# mixer.net
KiCad netlist of a schematic drawn in Altium Designer
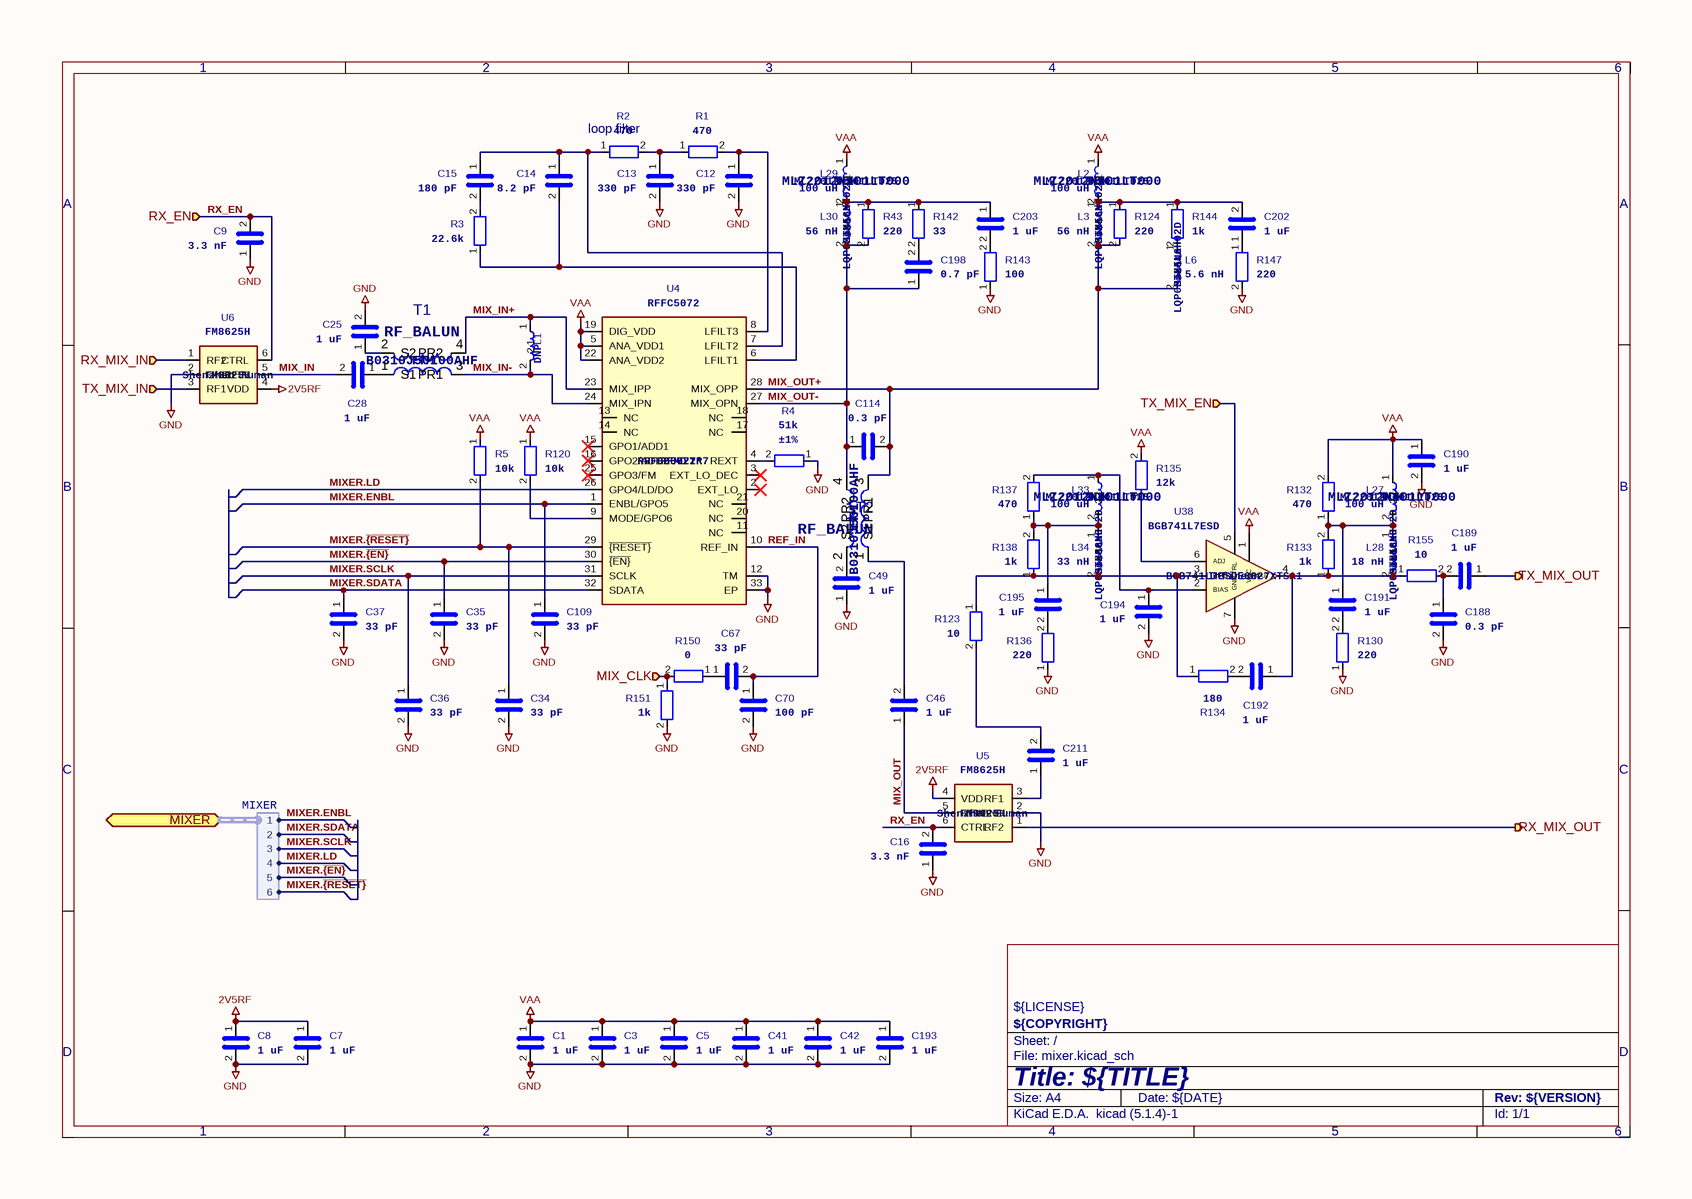
[diagram p0: mixer.SchDoc]

(export (version "E")
  (design (tool "Eeschema 10.0.6"))
  (components
    (comp (ref "C1")
      (value "1 uF")
      (footprint "C_0201_0603Metric")
      (fields (field (name "MANUFACTURER") "Murata") (field (name "PART NUMBER") "GRM033R61A105ME44D"))
      (libsource (lib "Device") (part "C"))
    )
    (comp (ref "C3")
      (value "1 uF")
      (footprint "C_0201_0603Metric")
      (fields (field (name "MANUFACTURER") "Murata") (field (name "PART NUMBER") "GRM033R61A105ME44D"))
      (libsource (lib "Device") (part "C"))
    )
    (comp (ref "C5")
      (value "1 uF")
      (footprint "C_0201_0603Metric")
      (fields (field (name "MANUFACTURER") "Murata") (field (name "PART NUMBER") "GRM033R61A105ME44D"))
      (libsource (lib "Device") (part "C"))
    )
    (comp (ref "C7")
      (value "1 uF")
      (footprint "C_0201_0603Metric")
      (fields (field (name "MANUFACTURER") "Murata") (field (name "PART NUMBER") "GRM033R61A105ME44D"))
      (libsource (lib "Device") (part "C"))
    )
    (comp (ref "C8")
      (value "1 uF")
      (footprint "C_0201_0603Metric")
      (fields (field (name "MANUFACTURER") "Murata") (field (name "PART NUMBER") "GRM033R61A105ME44D"))
      (libsource (lib "Device") (part "C"))
    )
    (comp (ref "C9")
      (value "3.3 nF")
      (footprint "C_0201_0603Metric")
      (fields (field (name "MANUFACTURER") "Murata") (field (name "PART NUMBER") "GRM033R71A332KA01D"))
      (libsource (lib "Device") (part "C"))
    )
    (comp (ref "C12")
      (value "330 pF")
      (footprint "C_0201_0603Metric")
      (fields (field (name "MANUFACTURER") "Murata") (field (name "PART NUMBER") "GRM0335C1E331JA01D"))
      (libsource (lib "Device") (part "C"))
    )
    (comp (ref "C13")
      (value "330 pF")
      (footprint "C_0201_0603Metric")
      (fields (field (name "MANUFACTURER") "Murata") (field (name "PART NUMBER") "GRM0335C1E331JA01D"))
      (libsource (lib "Device") (part "C"))
    )
    (comp (ref "C14")
      (value "8.2 pF")
      (footprint "C_0201_0603Metric")
      (fields (field (name "MANUFACTURER") "Murata") (field (name "PART NUMBER") "GRM0335C1H8R2CA01D"))
      (libsource (lib "Device") (part "C"))
    )
    (comp (ref "C15")
      (value "180 pF")
      (footprint "C_0201_0603Metric")
      (fields (field (name "MANUFACTURER") "Murata") (field (name "PART NUMBER") "GRM0335C1H181JA01D"))
      (libsource (lib "Device") (part "C"))
    )
    (comp (ref "C16")
      (value "3.3 nF")
      (footprint "C_0201_0603Metric")
      (fields (field (name "MANUFACTURER") "Murata") (field (name "PART NUMBER") "GRM033R71A332KA01D"))
      (libsource (lib "Device") (part "C"))
    )
    (comp (ref "C25")
      (value "1 uF")
      (footprint "C_0201_0603Metric")
      (fields (field (name "MANUFACTURER") "Murata") (field (name "PART NUMBER") "GRM033R61A105ME44D"))
      (libsource (lib "Device") (part "C"))
    )
    (comp (ref "C28")
      (value "1 uF")
      (footprint "C_0201_0603Metric")
      (fields (field (name "MANUFACTURER") "Murata") (field (name "PART NUMBER") "GRM033R61A105ME44D"))
      (libsource (lib "Device") (part "C"))
    )
    (comp (ref "C34")
      (value "33 pF")
      (footprint "C_0201_0603Metric")
      (fields (field (name "MANUFACTURER") "Murata") (field (name "PART NUMBER") "GRM0335C1H330JA01D"))
      (libsource (lib "Device") (part "C"))
    )
    (comp (ref "C35")
      (value "33 pF")
      (footprint "C_0201_0603Metric")
      (fields (field (name "MANUFACTURER") "Murata") (field (name "PART NUMBER") "GRM0335C1H330JA01D"))
      (libsource (lib "Device") (part "C"))
    )
    (comp (ref "C36")
      (value "33 pF")
      (footprint "C_0201_0603Metric")
      (fields (field (name "MANUFACTURER") "Murata") (field (name "PART NUMBER") "GRM0335C1H330JA01D"))
      (libsource (lib "Device") (part "C"))
    )
    (comp (ref "C37")
      (value "33 pF")
      (footprint "C_0201_0603Metric")
      (fields (field (name "MANUFACTURER") "Murata") (field (name "PART NUMBER") "GRM0335C1H330JA01D"))
      (libsource (lib "Device") (part "C"))
    )
    (comp (ref "C41")
      (value "1 uF")
      (footprint "C_0201_0603Metric")
      (fields (field (name "MANUFACTURER") "Murata") (field (name "PART NUMBER") "GRM033R61A105ME44D"))
      (libsource (lib "Device") (part "C"))
    )
    (comp (ref "C42")
      (value "1 uF")
      (footprint "C_0201_0603Metric")
      (fields (field (name "MANUFACTURER") "Murata") (field (name "PART NUMBER") "GRM033R61A105ME44D"))
      (libsource (lib "Device") (part "C"))
    )
    (comp (ref "C46")
      (value "1 uF")
      (footprint "C_0201_0603Metric")
      (fields (field (name "MANUFACTURER") "Murata") (field (name "PART NUMBER") "GRM033R61A105ME44D"))
      (libsource (lib "Device") (part "C"))
    )
    (comp (ref "C49")
      (value "1 uF")
      (footprint "C_0201_0603Metric")
      (fields (field (name "MANUFACTURER") "Murata") (field (name "PART NUMBER") "GRM033R61A105ME44D"))
      (libsource (lib "Device") (part "C"))
    )
    (comp (ref "C67")
      (value "33 pF")
      (footprint "C_0201_0603Metric")
      (fields (field (name "MANUFACTURER") "Murata") (field (name "PART NUMBER") "GRM0335C1H330JA01D"))
      (libsource (lib "Device") (part "C"))
    )
    (comp (ref "C70")
      (value "100 pF")
      (footprint "C_0201_0603Metric")
      (fields (field (name "MANUFACTURER") "Murata") (field (name "PART NUMBER") "GRM0335C1E101JA01D"))
      (libsource (lib "Device") (part "C"))
    )
    (comp (ref "C109")
      (value "33 pF")
      (footprint "C_0201_0603Metric")
      (fields (field (name "MANUFACTURER") "Murata") (field (name "PART NUMBER") "GRM0335C1H330JA01D"))
      (libsource (lib "Device") (part "C"))
    )
    (comp (ref "C114")
      (value "0.3 pF")
      (footprint "C_0201_0603Metric")
      (fields (field (name "MANUFACTURER") "Murata") (field (name "PART NUMBER") "GRM0335C1ER30BA01D"))
      (libsource (lib "Device") (part "C"))
    )
    (comp (ref "C188")
      (value "0.3 pF")
      (footprint "C_0201_0603Metric")
      (fields (field (name "MANUFACTURER") "Murata") (field (name "PART NUMBER") "GRM0335C1ER30BA01D"))
      (libsource (lib "Device") (part "C"))
    )
    (comp (ref "C189")
      (value "1 uF")
      (footprint "C_0201_0603Metric")
      (fields (field (name "MANUFACTURER") "Murata") (field (name "PART NUMBER") "GRM033R61A105ME44D"))
      (libsource (lib "Device") (part "C"))
    )
    (comp (ref "C190")
      (value "1 uF")
      (footprint "C_0201_0603Metric")
      (fields (field (name "MANUFACTURER") "Murata") (field (name "PART NUMBER") "GRM033R61A105ME44D"))
      (libsource (lib "Device") (part "C"))
    )
    (comp (ref "C191")
      (value "1 uF")
      (footprint "C_0201_0603Metric")
      (fields (field (name "MANUFACTURER") "Murata") (field (name "PART NUMBER") "GRM033R61A105ME44D"))
      (libsource (lib "Device") (part "C"))
    )
    (comp (ref "C192")
      (value "1 uF")
      (footprint "C_0201_0603Metric")
      (fields (field (name "MANUFACTURER") "Murata") (field (name "PART NUMBER") "GRM033R61A105ME44D"))
      (libsource (lib "Device") (part "C"))
    )
    (comp (ref "C193")
      (value "1 uF")
      (footprint "C_0201_0603Metric")
      (fields (field (name "MANUFACTURER") "Murata") (field (name "PART NUMBER") "GRM033R61A105ME44D"))
      (libsource (lib "Device") (part "C"))
    )
    (comp (ref "C194")
      (value "1 uF")
      (footprint "C_0201_0603Metric")
      (fields (field (name "MANUFACTURER") "Murata") (field (name "PART NUMBER") "GRM033R61A105ME44D"))
      (libsource (lib "Device") (part "C"))
    )
    (comp (ref "C195")
      (value "1 uF")
      (footprint "C_0201_0603Metric")
      (fields (field (name "MANUFACTURER") "Murata") (field (name "PART NUMBER") "GRM033R61A105ME44D"))
      (libsource (lib "Device") (part "C"))
    )
    (comp (ref "C198")
      (value "0.7 pF")
      (footprint "C_0201_0603Metric")
      (fields (field (name "MANUFACTURER") "Murata") (field (name "PART NUMBER") "GRM0335C1ER70WA01D"))
      (libsource (lib "Device") (part "C"))
    )
    (comp (ref "C202")
      (value "1 uF")
      (footprint "C_0201_0603Metric")
      (fields (field (name "MANUFACTURER") "Murata") (field (name "PART NUMBER") "GRM033R61A105ME44D"))
      (libsource (lib "Device") (part "C"))
    )
    (comp (ref "C203")
      (value "1 uF")
      (footprint "C_0201_0603Metric")
      (fields (field (name "MANUFACTURER") "Murata") (field (name "PART NUMBER") "GRM033R61A105ME44D"))
      (libsource (lib "Device") (part "C"))
    )
    (comp (ref "C211")
      (value "1 uF")
      (footprint "C_0201_0603Metric")
      (fields (field (name "MANUFACTURER") "Murata") (field (name "PART NUMBER") "GRM033R61A105ME44D"))
      (libsource (lib "Device") (part "C"))
    )
    (comp (ref "L1") (value "DNP") (footprint "L_0201_0603Metric") (libsource (lib "Device") (part "L")))
    (comp (ref "L2")
      (value "100 uH")
      (footprint "L_TDK_MLZ2012_h1.25mm")
      (fields
        (field (name "MANUFACTURER") "TDK")
        (field (name "PART NUMBER") "MLZ2012N101LT000")
        (field (name "SUBSTITUTION") "MLZ2012N101LTD25")
      )
      (libsource (lib "") (part "L_1"))
    )
    (comp (ref "L3")
      (value "56 nH")
      (footprint "L_0201_0603Metric")
      (fields
        (field (name "MANUFACTURER") "Murata")
        (field (name "PART NUMBER") "LQP03TN56NJ02D")
        (field (name "SUBSTITUTION") "LQP03TN56NH02D")
      )
      (libsource (lib "Device") (part "L"))
    )
    (comp (ref "L6")
      (value "5.6 nH")
      (footprint "L_0201_0603Metric")
      (fields (field (name "MANUFACTURER") "Murata") (field (name "PART NUMBER") "LQP03TN5N6H02D"))
      (libsource (lib "Device") (part "L"))
    )
    (comp (ref "L27")
      (value "100 uH")
      (footprint "L_TDK_MLZ2012_h1.25mm")
      (fields
        (field (name "MANUFACTURER") "TDK")
        (field (name "PART NUMBER") "MLZ2012N101LT000")
        (field (name "SUBSTITUTION") "MLZ2012N101LTD25")
      )
      (libsource (lib "Device") (part "L"))
    )
    (comp (ref "L28")
      (value "18 nH")
      (footprint "L_0201_0603Metric")
      (fields
        (field (name "MANUFACTURER") "Murata")
        (field (name "PART NUMBER") "LQP03TN18NJ02D")
        (field (name "SUBSTITUTION") "LQP03TN56NH02D")
      )
      (libsource (lib "Device") (part "L"))
    )
    (comp (ref "L29")
      (value "100 uH")
      (footprint "L_TDK_MLZ2012_h1.25mm")
      (fields
        (field (name "MANUFACTURER") "TDK")
        (field (name "PART NUMBER") "MLZ2012N101LT000")
        (field (name "SUBSTITUTION") "MLZ2012N101LTD25")
      )
      (libsource (lib "") (part "L_1"))
    )
    (comp (ref "L30")
      (value "56 nH")
      (footprint "L_0201_0603Metric")
      (fields
        (field (name "MANUFACTURER") "Murata")
        (field (name "PART NUMBER") "LQP03TN56NJ02D")
        (field (name "SUBSTITUTION") "LQP03TN56NH02D")
      )
      (libsource (lib "Device") (part "L"))
    )
    (comp (ref "L33")
      (value "100 uH")
      (footprint "L_TDK_MLZ2012_h1.25mm")
      (fields
        (field (name "MANUFACTURER") "TDK")
        (field (name "PART NUMBER") "MLZ2012N101LT000")
        (field (name "SUBSTITUTION") "MLZ2012N101LTD25")
      )
      (libsource (lib "Device") (part "L"))
    )
    (comp (ref "L34")
      (value "33 nH")
      (footprint "L_0201_0603Metric")
      (fields
        (field (name "MANUFACTURER") "Murata")
        (field (name "PART NUMBER") "LQP03TN33NJ02D")
        (field (name "SUBSTITUTION") "LQP03TN56NH02D")
      )
      (libsource (lib "Device") (part "L"))
    )
    (comp (ref "R1")
      (value "470")
      (footprint "R_0201_0603Metric")
      (fields (field (name "MANUFACTURER") "Yageo") (field (name "PART NUMBER") "RC0201JR-07470RL"))
      (libsource (lib "Device") (part "R"))
    )
    (comp (ref "R2")
      (value "470")
      (footprint "R_0201_0603Metric")
      (fields (field (name "MANUFACTURER") "Yageo") (field (name "PART NUMBER") "RC0201JR-07470RL"))
      (libsource (lib "Device") (part "R"))
    )
    (comp (ref "R3")
      (value "22.6k")
      (footprint "R_0201_0603Metric")
      (fields (field (name "MANUFACTURER") "Yageo") (field (name "PART NUMBER") "RC0201FR-0722K6L"))
      (libsource (lib "") (part "R_1"))
    )
    (comp (ref "R4")
      (value "51k")
      (footprint "R_0201_0603Metric")
      (fields
        (field (name "MANUFACTURER") "Yageo")
        (field (name "PART NUMBER") "RC0201FR-0751KL")
        (field (name "TOLERANCE") "±1%")
      )
      (libsource (lib "") (part "R_3"))
    )
    (comp (ref "R5")
      (value "10k")
      (footprint "R_0402_1005Metric")
      (fields (field (name "MANUFACTURER") "Yageo") (field (name "PART NUMBER") "RC0402JR-0710KL"))
      (libsource (lib "") (part "R_2"))
    )
    (comp (ref "R43")
      (value "220")
      (footprint "R_0201_0603Metric")
      (fields (field (name "MANUFACTURER") "Yageo") (field (name "PART NUMBER") "RC0201JR-07220RL"))
      (libsource (lib "") (part "R_2"))
    )
    (comp (ref "R120")
      (value "10k")
      (footprint "R_0402_1005Metric")
      (fields (field (name "MANUFACTURER") "Yageo") (field (name "PART NUMBER") "RC0402JR-0710KL"))
      (libsource (lib "") (part "R_2"))
    )
    (comp (ref "R123")
      (value "10")
      (footprint "R_0201_0603Metric")
      (fields (field (name "MANUFACTURER") "Yageo") (field (name "PART NUMBER") "RC0201JR-0710RL"))
      (libsource (lib "") (part "R_2"))
    )
    (comp (ref "R124")
      (value "220")
      (footprint "R_0201_0603Metric")
      (fields (field (name "MANUFACTURER") "Yageo") (field (name "PART NUMBER") "RC0201JR-07220RL"))
      (libsource (lib "") (part "R_2"))
    )
    (comp (ref "R130")
      (value "220")
      (footprint "R_0201_0603Metric")
      (fields (field (name "MANUFACTURER") "Yageo") (field (name "PART NUMBER") "RC0201JR-07220RL"))
      (libsource (lib "Device") (part "R"))
    )
    (comp (ref "R132")
      (value "470")
      (footprint "R_0201_0603Metric")
      (fields (field (name "MANUFACTURER") "Yageo") (field (name "PART NUMBER") "RC0201JR-07470RL"))
      (libsource (lib "") (part "R_1"))
    )
    (comp (ref "R133")
      (value "1k")
      (footprint "R_0201_0603Metric")
      (fields (field (name "MANUFACTURER") "Yageo") (field (name "PART NUMBER") "RC0201FR-071KL"))
      (libsource (lib "") (part "R_1"))
    )
    (comp (ref "R134")
      (value "180")
      (footprint "R_0201_0603Metric")
      (fields (field (name "MANUFACTURER") "Yageo") (field (name "PART NUMBER") "RC0201JR-07180RL"))
      (libsource (lib "Device") (part "R"))
    )
    (comp (ref "R135")
      (value "12k")
      (footprint "R_0201_0603Metric")
      (fields (field (name "PART NUMBER") "RC0201FR-0712KL") (field (name "MANUFACTURER") "Yageo"))
      (libsource (lib "Device") (part "R"))
    )
    (comp (ref "R136")
      (value "220")
      (footprint "R_0201_0603Metric")
      (fields (field (name "MANUFACTURER") "Yageo") (field (name "PART NUMBER") "RC0201JR-07220RL"))
      (libsource (lib "") (part "R_1"))
    )
    (comp (ref "R137")
      (value "470")
      (footprint "R_0201_0603Metric")
      (fields (field (name "MANUFACTURER") "Yageo") (field (name "PART NUMBER") "RC0201JR-07470RL"))
      (libsource (lib "") (part "R_1"))
    )
    (comp (ref "R138")
      (value "1k")
      (footprint "R_0201_0603Metric")
      (fields (field (name "MANUFACTURER") "Yageo") (field (name "PART NUMBER") "RC0201FR-071KL"))
      (libsource (lib "") (part "R_1"))
    )
    (comp (ref "R142")
      (value "33")
      (footprint "R_0201_0603Metric")
      (fields (field (name "MANUFACTURER") "Yageo") (field (name "PART NUMBER") "RC0201JR-0733RL"))
      (libsource (lib "") (part "R_3"))
    )
    (comp (ref "R143")
      (value "100")
      (footprint "R_0201_0603Metric")
      (fields (field (name "MANUFACTURER") "Yageo") (field (name "PART NUMBER") "RC0201JR-07100RL"))
      (libsource (lib "Device") (part "R"))
    )
    (comp (ref "R144")
      (value "1k")
      (footprint "R_0201_0603Metric")
      (fields (field (name "MANUFACTURER") "Yageo") (field (name "PART NUMBER") "RC0201FR-071KL"))
      (libsource (lib "") (part "R_3"))
    )
    (comp (ref "R147")
      (value "220")
      (footprint "R_0201_0603Metric")
      (fields (field (name "MANUFACTURER") "Yageo") (field (name "PART NUMBER") "RC0201JR-07220RL"))
      (libsource (lib "") (part "R_2"))
    )
    (comp (ref "R150")
      (value "0")
      (footprint "R_0201_0603Metric")
      (fields (field (name "MANUFACTURER") "Yageo") (field (name "PART NUMBER") "RC0201JR-070RL"))
      (libsource (lib "") (part "R_2"))
    )
    (comp (ref "R151")
      (value "1k")
      (footprint "R_0201_0603Metric")
      (fields (field (name "MANUFACTURER") "Yageo") (field (name "PART NUMBER") "RC0201FR-071KL"))
      (libsource (lib "") (part "R_3"))
    )
    (comp (ref "R155")
      (value "10")
      (footprint "R_0201_0603Metric")
      (fields (field (name "MANUFACTURER") "Yageo") (field (name "PART NUMBER") "RC0201JR-0710RL"))
      (libsource (lib "") (part "R_1"))
    )
    (comp (ref "T1")
      (value "RF_BALUN")
      (footprint "Anaren_0805_2012Metric-6")
      (fields (field (name "MANUFACTURER") "TTM") (field (name "PART NUMBER") "B0310J50100AHF"))
      (libsource (lib "hackrf") (part "BALUN-B0310J50100AHF"))
    )
    (comp (ref "T2")
      (value "RF_BALUN")
      (footprint "Anaren_0805_2012Metric-6")
      (fields (field (name "MANUFACTURER") "TTM") (field (name "PART NUMBER") "B0310J50100AHF"))
      (libsource (lib "hackrf") (part "BALUN-B0310J50100AHF"))
    )
    (comp (ref "U4")
      (value "RFFC5072")
      (footprint "QFN-32-1EP_5x5mm_P0.5mm_EP3.7x3.7mm_ThermalVias")
      (fields
        (field (name "MANUFACTURER") "RFMD")
        (field (name "PART NUMBER") "RFFC5072TR7")
        (field (name "SUBSTITUTION") "RFFC5072*")
      )
      (libsource (lib "praline") (part "RFFC5072"))
    )
    (comp (ref "U5")
      (value "FM8625H")
      (footprint "TSLP-6-4_1.1x0.7mm_P0.4mm")
      (fields (field (name "MANUFACTURER") "Shenzhen Fuman") (field (name "PART NUMBER") "FM8625H"))
      (libsource (lib "") (part "BGS12P2L6_1"))
    )
    (comp (ref "U6")
      (value "FM8625H")
      (footprint "TSLP-6-4_1.1x0.7mm_P0.4mm")
      (fields (field (name "MANUFACTURER") "Shenzhen Fuman") (field (name "PART NUMBER") "FM8625H"))
      (libsource (lib "praline") (part "BGS12P2L6"))
    )
    (comp (ref "U38")
      (value "BGB741L7ESD")
      (footprint "TSLP-7-1")
      (fields (field (name "MANUFACTURER") "Infineon") (field (name "PART NUMBER") "BGB741L7ESDE6327XTSA1"))
      (libsource (lib "praline") (part "BGB741L7ESD"))
    )
  )
  (nets
    (net (code "2") (name "/MIXER.ENBL") (class "Default")
      (node (ref "C109") (pin "1") (pinfunction "1_1") (pintype "passive"))
      (node (ref "U4") (pin "1") (pinfunction "ENBL/GPO5_1") (pintype "passive"))
    )
    (net (code "3") (name "/MIXER.LD") (class "Default")
      (node (ref "U4") (pin "26") (pinfunction "GPO4/LD/DO_26") (pintype "passive"))
    )
    (net (code "4") (name "/MIXER.SCLK") (class "Default")
      (node (ref "C36") (pin "1") (pinfunction "1_1") (pintype "passive"))
      (node (ref "U4") (pin "31") (pinfunction "SCLK_31") (pintype "passive"))
    )
    (net (code "5") (name "/MIXER.SDATA") (class "Default")
      (node (ref "C37") (pin "1") (pinfunction "1_1") (pintype "passive"))
      (node (ref "U4") (pin "32") (pinfunction "SDATA_32") (pintype "passive"))
    )
    (net (code "6") (name "/MIXER.~{{EN}}") (class "Default")
      (node (ref "C35") (pin "1") (pinfunction "1_1") (pintype "passive"))
      (node (ref "U4") (pin "30") (pinfunction "~{{EN}}_30") (pintype "passive"))
    )
    (net (code "7") (name "/MIXER.~{{RESET}}") (class "Default")
      (node (ref "C34") (pin "1") (pinfunction "1_1") (pintype "passive"))
      (node (ref "R5") (pin "2") (pinfunction "2_2") (pintype "passive"))
      (node (ref "U4") (pin "29") (pinfunction "~{{RESET}}_29") (pintype "passive"))
    )
    (net (code "8") (name "/MIX_CLK") (class "Default")
      (node (ref "R150") (pin "2") (pinfunction "2_2") (pintype "passive"))
      (node (ref "R151") (pin "1") (pinfunction "1_1") (pintype "passive"))
    )
    (net (code "9") (name "/MIX_IN") (class "Default")
      (node (ref "C28") (pin "2") (pinfunction "2_2") (pintype "passive"))
      (node (ref "U6") (pin "5") (pinfunction "RFIN_5") (pintype "passive"))
    )
    (net (code "10") (name "/MIX_IN+") (class "Default")
      (node (ref "L1") (pin "1") (pinfunction "1_1") (pintype "passive"))
      (node (ref "T1") (pin "4") (pinfunction "PR2_4") (pintype "passive"))
      (node (ref "U4") (pin "23") (pinfunction "MIX_IPP_23") (pintype "passive"))
    )
    (net (code "11") (name "/MIX_IN-") (class "Default")
      (node (ref "L1") (pin "2") (pinfunction "2_2") (pintype "passive"))
      (node (ref "T1") (pin "3") (pinfunction "PR1_3") (pintype "passive"))
      (node (ref "U4") (pin "24") (pinfunction "MIX_IPN_24") (pintype "passive"))
    )
    (net (code "12") (name "/MIX_OUT") (class "Default")
      (node (ref "C46") (pin "1") (pinfunction "1_1") (pintype "passive"))
      (node (ref "U5") (pin "5") (pinfunction "RFIN_5") (pintype "passive"))
    )
    (net (code "13") (name "/MIX_OUT+") (class "Default")
      (node (ref "C114") (pin "2") (pinfunction "2_2") (pintype "passive"))
      (node (ref "L3") (pin "2") (pinfunction "2_2") (pintype "passive"))
      (node (ref "L6") (pin "2") (pinfunction "2_2") (pintype "passive"))
      (node (ref "R124") (pin "2") (pinfunction "2_2") (pintype "passive"))
      (node (ref "T2") (pin "3") (pinfunction "PR1_3") (pintype "passive"))
      (node (ref "U4") (pin "28") (pinfunction "MIX_OPP_28") (pintype "passive"))
    )
    (net (code "14") (name "/MIX_OUT-") (class "Default")
      (node (ref "C114") (pin "1") (pinfunction "1_1") (pintype "passive"))
      (node (ref "C198") (pin "1") (pinfunction "1_1") (pintype "passive"))
      (node (ref "L30") (pin "2") (pinfunction "2_2") (pintype "passive"))
      (node (ref "R43") (pin "2") (pinfunction "2_2") (pintype "passive"))
      (node (ref "T2") (pin "4") (pinfunction "PR2_4") (pintype "passive"))
      (node (ref "U4") (pin "27") (pinfunction "MIX_OPN_27") (pintype "passive"))
    )
    (net (code "15") (name "/REF_IN") (class "Default")
      (node (ref "C67") (pin "2") (pinfunction "2_2") (pintype "passive"))
      (node (ref "C70") (pin "1") (pinfunction "1_1") (pintype "passive"))
      (node (ref "U4") (pin "10") (pinfunction "REF_IN_10") (pintype "passive"))
    )
    (net (code "16") (name "/RX_EN") (class "Default")
      (node (ref "C16") (pin "2") (pinfunction "2_2") (pintype "passive"))
      (node (ref "C9") (pin "2") (pinfunction "2_2") (pintype "passive"))
      (node (ref "U5") (pin "6") (pinfunction "CTRL_6") (pintype "passive"))
      (node (ref "U6") (pin "6") (pinfunction "CTRL_6") (pintype "passive"))
    )
    (net (code "17") (name "/RX_MIX_IN") (class "Default")
      (node (ref "U6") (pin "1") (pinfunction "RF2_1") (pintype "passive"))
    )
    (net (code "18") (name "/RX_MIX_OUT") (class "Default")
      (node (ref "U5") (pin "1") (pinfunction "RF2_1") (pintype "passive"))
    )
    (net (code "19") (name "/TX_MIX_EN") (class "Default")
      (node (ref "U38") (pin "5") (pinfunction "CTRL_5") (pintype "passive"))
    )
    (net (code "20") (name "/TX_MIX_IN") (class "Default")
      (node (ref "U6") (pin "3") (pinfunction "RF1_3") (pintype "passive"))
    )
    (net (code "21") (name "/TX_MIX_OUT") (class "Default")
      (node (ref "C189") (pin "1") (pinfunction "1_1") (pintype "passive"))
    )
    (net (code "23") (name "2V5RF") (class "Default")
      (node (ref "C7") (pin "1") (pinfunction "1_1") (pintype "passive"))
      (node (ref "C8") (pin "1") (pinfunction "1_1") (pintype "passive"))
      (node (ref "U5") (pin "4") (pinfunction "VDD_4") (pintype "passive"))
      (node (ref "U6") (pin "4") (pinfunction "VDD_4") (pintype "passive"))
    )
    (net (code "24") (name "GND") (class "Default")
      (node (ref "C1") (pin "2") (pinfunction "2_2") (pintype "passive"))
      (node (ref "C109") (pin "2") (pinfunction "2_2") (pintype "passive"))
      (node (ref "C12") (pin "2") (pinfunction "2_2") (pintype "passive"))
      (node (ref "C13") (pin "2") (pinfunction "2_2") (pintype "passive"))
      (node (ref "C16") (pin "1") (pinfunction "1_1") (pintype "passive"))
      (node (ref "C188") (pin "2") (pinfunction "2_2") (pintype "passive"))
      (node (ref "C190") (pin "2") (pinfunction "2_2") (pintype "passive"))
      (node (ref "C193") (pin "2") (pinfunction "2_2") (pintype "passive"))
      (node (ref "C194") (pin "2") (pinfunction "2_2") (pintype "passive"))
      (node (ref "C25") (pin "2") (pinfunction "2_2") (pintype "passive"))
      (node (ref "C3") (pin "2") (pinfunction "2_2") (pintype "passive"))
      (node (ref "C34") (pin "2") (pinfunction "2_2") (pintype "passive"))
      (node (ref "C35") (pin "2") (pinfunction "2_2") (pintype "passive"))
      (node (ref "C36") (pin "2") (pinfunction "2_2") (pintype "passive"))
      (node (ref "C37") (pin "2") (pinfunction "2_2") (pintype "passive"))
      (node (ref "C41") (pin "2") (pinfunction "2_2") (pintype "passive"))
      (node (ref "C42") (pin "2") (pinfunction "2_2") (pintype "passive"))
      (node (ref "C49") (pin "1") (pinfunction "1_1") (pintype "passive"))
      (node (ref "C5") (pin "2") (pinfunction "2_2") (pintype "passive"))
      (node (ref "C7") (pin "2") (pinfunction "2_2") (pintype "passive"))
      (node (ref "C70") (pin "2") (pinfunction "2_2") (pintype "passive"))
      (node (ref "C8") (pin "2") (pinfunction "2_2") (pintype "passive"))
      (node (ref "C9") (pin "1") (pinfunction "1_1") (pintype "passive"))
      (node (ref "R130") (pin "1") (pinfunction "1_1") (pintype "passive"))
      (node (ref "R136") (pin "1") (pinfunction "1_1") (pintype "passive"))
      (node (ref "R143") (pin "1") (pinfunction "1_1") (pintype "passive"))
      (node (ref "R147") (pin "2") (pinfunction "2_2") (pintype "passive"))
      (node (ref "R151") (pin "2") (pinfunction "2_2") (pintype "passive"))
      (node (ref "R4") (pin "1") (pinfunction "1_1") (pintype "passive"))
      (node (ref "U38") (pin "7") (pinfunction "GND_7") (pintype "passive"))
      (node (ref "U4") (pin "12") (pinfunction "TM_12") (pintype "passive"))
      (node (ref "U4") (pin "33") (pinfunction "EP_33") (pintype "passive"))
      (node (ref "U5") (pin "2") (pinfunction "GND_2") (pintype "passive"))
      (node (ref "U6") (pin "2") (pinfunction "GND_2") (pintype "passive"))
    )
    (net (code "25") (name "Net-(C13-Pad1)") (class "Default")
      (node (ref "C13") (pin "1") (pinfunction "1_1") (pintype "passive"))
      (node (ref "R1") (pin "1") (pinfunction "1_1") (pintype "passive"))
      (node (ref "R2") (pin "2") (pinfunction "2_2") (pintype "passive"))
    )
    (net (code "26") (name "Net-(C15-Pad2)") (class "Default")
      (node (ref "C15") (pin "2") (pinfunction "2_2") (pintype "passive"))
      (node (ref "R3") (pin "2") (pinfunction "2_2") (pintype "passive"))
    )
    (net (code "27") (name "Net-(C67-Pad1)") (class "Default")
      (node (ref "C67") (pin "1") (pinfunction "1_1") (pintype "passive"))
      (node (ref "R150") (pin "1") (pinfunction "1_1") (pintype "passive"))
    )
    (net (code "28") (name "Net-(C188-Pad1)") (class "Default")
      (node (ref "C188") (pin "1") (pinfunction "1_1") (pintype "passive"))
      (node (ref "C189") (pin "2") (pinfunction "2_2") (pintype "passive"))
      (node (ref "R155") (pin "2") (pinfunction "2_2") (pintype "passive"))
    )
    (net (code "29") (name "Net-(C191-Pad1)") (class "Default")
      (node (ref "C191") (pin "1") (pinfunction "1_1") (pintype "passive"))
      (node (ref "L27") (pin "2") (pinfunction "2_2") (pintype "passive"))
      (node (ref "L28") (pin "1") (pinfunction "1_1") (pintype "passive"))
      (node (ref "R132") (pin "1") (pinfunction "1_1") (pintype "passive"))
      (node (ref "R133") (pin "2") (pinfunction "2_2") (pintype "passive"))
    )
    (net (code "30") (name "Net-(C191-Pad2)") (class "Default")
      (node (ref "C191") (pin "2") (pinfunction "2_2") (pintype "passive"))
      (node (ref "R130") (pin "2") (pinfunction "2_2") (pintype "passive"))
    )
    (net (code "31") (name "Net-(C192-Pad2)") (class "Default")
      (node (ref "C192") (pin "2") (pinfunction "2_2") (pintype "passive"))
      (node (ref "R134") (pin "2") (pinfunction "2_2") (pintype "passive"))
    )
    (net (code "32") (name "Net-(C195-Pad1)") (class "Default")
      (node (ref "C195") (pin "1") (pinfunction "1_1") (pintype "passive"))
      (node (ref "L33") (pin "2") (pinfunction "2_2") (pintype "passive"))
      (node (ref "L34") (pin "1") (pinfunction "1_1") (pintype "passive"))
      (node (ref "R137") (pin "1") (pinfunction "1_1") (pintype "passive"))
      (node (ref "R138") (pin "2") (pinfunction "2_2") (pintype "passive"))
    )
    (net (code "33") (name "Net-(C195-Pad2)") (class "Default")
      (node (ref "C195") (pin "2") (pinfunction "2_2") (pintype "passive"))
      (node (ref "R136") (pin "2") (pinfunction "2_2") (pintype "passive"))
    )
    (net (code "34") (name "Net-(C198-Pad2)") (class "Default")
      (node (ref "C198") (pin "2") (pinfunction "2_2") (pintype "passive"))
      (node (ref "R142") (pin "2") (pinfunction "2_2") (pintype "passive"))
    )
    (net (code "35") (name "Net-(C202-Pad1)") (class "Default")
      (node (ref "C202") (pin "1") (pinfunction "1_1") (pintype "passive"))
      (node (ref "R147") (pin "1") (pinfunction "1_1") (pintype "passive"))
    )
    (net (code "36") (name "Net-(C202-Pad2)") (class "Default")
      (node (ref "C202") (pin "2") (pinfunction "2_2") (pintype "passive"))
      (node (ref "L2") (pin "2") (pinfunction "2_2") (pintype "passive"))
      (node (ref "L3") (pin "1") (pinfunction "1_1") (pintype "passive"))
      (node (ref "R124") (pin "1") (pinfunction "1_1") (pintype "passive"))
      (node (ref "R144") (pin "1") (pinfunction "1_1") (pintype "passive"))
    )
    (net (code "37") (name "Net-(C203-Pad1)") (class "Default")
      (node (ref "C203") (pin "1") (pinfunction "1_1") (pintype "passive"))
      (node (ref "L29") (pin "2") (pinfunction "2_2") (pintype "passive"))
      (node (ref "L30") (pin "1") (pinfunction "1_1") (pintype "passive"))
      (node (ref "R142") (pin "1") (pinfunction "1_1") (pintype "passive"))
      (node (ref "R43") (pin "1") (pinfunction "1_1") (pintype "passive"))
    )
    (net (code "38") (name "Net-(C203-Pad2)") (class "Default")
      (node (ref "C203") (pin "2") (pinfunction "2_2") (pintype "passive"))
      (node (ref "R143") (pin "2") (pinfunction "2_2") (pintype "passive"))
    )
    (net (code "39") (name "Net-(C211-Pad2)") (class "Default")
      (node (ref "C211") (pin "2") (pinfunction "2_2") (pintype "passive"))
      (node (ref "R123") (pin "2") (pinfunction "2_2") (pintype "passive"))
    )
    (net (code "40") (name "Net-(L6-Pad1)") (class "Default")
      (node (ref "L6") (pin "1") (pinfunction "1_1") (pintype "passive"))
      (node (ref "R144") (pin "2") (pinfunction "2_2") (pintype "passive"))
    )
    (net (code "41") (name "Net-(T1-S1)") (class "Default")
      (node (ref "C28") (pin "1") (pinfunction "1_1") (pintype "passive"))
      (node (ref "T1") (pin "1") (pinfunction "S1_1") (pintype "passive"))
    )
    (net (code "42") (name "Net-(T1-S2)") (class "Default")
      (node (ref "C25") (pin "1") (pinfunction "1_1") (pintype "passive"))
      (node (ref "T1") (pin "2") (pinfunction "S2_2") (pintype "passive"))
    )
    (net (code "43") (name "Net-(T2-S1)") (class "Default")
      (node (ref "C46") (pin "2") (pinfunction "2_2") (pintype "passive"))
      (node (ref "T2") (pin "1") (pinfunction "S1_1") (pintype "passive"))
    )
    (net (code "44") (name "Net-(T2-S2)") (class "Default")
      (node (ref "C49") (pin "2") (pinfunction "2_2") (pintype "passive"))
      (node (ref "T2") (pin "2") (pinfunction "S2_2") (pintype "passive"))
    )
    (net (code "45") (name "Net-(U4-LFILT1)") (class "Default")
      (node (ref "C14") (pin "2") (pinfunction "2_2") (pintype "passive"))
      (node (ref "R3") (pin "1") (pinfunction "1_1") (pintype "passive"))
      (node (ref "U4") (pin "6") (pinfunction "LFILT1_6") (pintype "passive"))
    )
    (net (code "46") (name "Net-(U4-LFILT2)") (class "Default")
      (node (ref "C14") (pin "1") (pinfunction "1_1") (pintype "passive"))
      (node (ref "C15") (pin "1") (pinfunction "1_1") (pintype "passive"))
      (node (ref "R2") (pin "1") (pinfunction "1_1") (pintype "passive"))
      (node (ref "U4") (pin "7") (pinfunction "LFILT2_7") (pintype "passive"))
    )
    (net (code "47") (name "Net-(U4-LFILT3)") (class "Default")
      (node (ref "C12") (pin "1") (pinfunction "1_1") (pintype "passive"))
      (node (ref "R1") (pin "2") (pinfunction "2_2") (pintype "passive"))
      (node (ref "U4") (pin "8") (pinfunction "LFILT3_8") (pintype "passive"))
    )
    (net (code "48") (name "Net-(U4-MODE{slash}GPO6)") (class "Default")
      (node (ref "R120") (pin "2") (pinfunction "2_2") (pintype "passive"))
      (node (ref "U4") (pin "9") (pinfunction "MODE/GPO6_9") (pintype "passive"))
    )
    (net (code "49") (name "Net-(U4-REXT)") (class "Default")
      (node (ref "R4") (pin "2") (pinfunction "2_2") (pintype "passive"))
      (node (ref "U4") (pin "4") (pinfunction "REXT_4") (pintype "passive"))
    )
    (net (code "50") (name "Net-(U5-RF1)") (class "Default")
      (node (ref "C211") (pin "1") (pinfunction "1_1") (pintype "passive"))
      (node (ref "U5") (pin "3") (pinfunction "RF1_3") (pintype "passive"))
    )
    (net (code "51") (name "Net-(U38-ADJ)") (class "Default")
      (node (ref "R135") (pin "1") (pinfunction "1_1") (pintype "passive"))
      (node (ref "U38") (pin "6") (pinfunction "ADJ_6") (pintype "passive"))
    )
    (net (code "52") (name "Net-(U38-BIAS)") (class "Default")
      (node (ref "C194") (pin "1") (pinfunction "1_1") (pintype "passive"))
      (node (ref "L33") (pin "1") (pinfunction "1_1") (pintype "passive"))
      (node (ref "R137") (pin "2") (pinfunction "2_2") (pintype "passive"))
      (node (ref "U38") (pin "2") (pinfunction "BIAS_2") (pintype "passive"))
    )
    (net (code "53") (name "Net-(U38-RFIN)") (class "Default")
      (node (ref "L34") (pin "2") (pinfunction "2_2") (pintype "passive"))
      (node (ref "R123") (pin "1") (pinfunction "1_1") (pintype "passive"))
      (node (ref "R134") (pin "1") (pinfunction "1_1") (pintype "passive"))
      (node (ref "R138") (pin "1") (pinfunction "1_1") (pintype "passive"))
      (node (ref "U38") (pin "3") (pinfunction "RFIN_3") (pintype "passive"))
    )
    (net (code "54") (name "Net-(U38-RFOUT)") (class "Default")
      (node (ref "C192") (pin "1") (pinfunction "1_1") (pintype "passive"))
      (node (ref "L28") (pin "2") (pinfunction "2_2") (pintype "passive"))
      (node (ref "R133") (pin "1") (pinfunction "1_1") (pintype "passive"))
      (node (ref "R155") (pin "1") (pinfunction "1_1") (pintype "passive"))
      (node (ref "U38") (pin "4") (pinfunction "RFOUT_4") (pintype "passive"))
    )
    (net (code "55") (name "VAA") (class "Default")
      (node (ref "C1") (pin "1") (pinfunction "1_1") (pintype "passive"))
      (node (ref "C190") (pin "1") (pinfunction "1_1") (pintype "passive"))
      (node (ref "C193") (pin "1") (pinfunction "1_1") (pintype "passive"))
      (node (ref "C3") (pin "1") (pinfunction "1_1") (pintype "passive"))
      (node (ref "C41") (pin "1") (pinfunction "1_1") (pintype "passive"))
      (node (ref "C42") (pin "1") (pinfunction "1_1") (pintype "passive"))
      (node (ref "C5") (pin "1") (pinfunction "1_1") (pintype "passive"))
      (node (ref "L2") (pin "1") (pinfunction "1_1") (pintype "passive"))
      (node (ref "L27") (pin "1") (pinfunction "1_1") (pintype "passive"))
      (node (ref "L29") (pin "1") (pinfunction "1_1") (pintype "passive"))
      (node (ref "R120") (pin "1") (pinfunction "1_1") (pintype "passive"))
      (node (ref "R132") (pin "2") (pinfunction "2_2") (pintype "passive"))
      (node (ref "R135") (pin "2") (pinfunction "2_2") (pintype "passive"))
      (node (ref "R5") (pin "1") (pinfunction "1_1") (pintype "passive"))
      (node (ref "U38") (pin "1") (pinfunction "VCC_1") (pintype "passive"))
      (node (ref "U4") (pin "19") (pinfunction "DIG_VDD_19") (pintype "passive"))
      (node (ref "U4") (pin "22") (pinfunction "ANA_VDD2_22") (pintype "passive"))
      (node (ref "U4") (pin "5") (pinfunction "ANA_VDD1_5") (pintype "passive"))
    )
    (net (code "56") (name "unconnected-(U4-EXT_LO-Pad2)") (class "Default")
      (node (ref "U4") (pin "2") (pinfunction "EXT_LO_2") (pintype "passive+no_connect"))
    )
    (net (code "57") (name "unconnected-(U4-EXT_LO_DEC-Pad3)") (class "Default")
      (node (ref "U4") (pin "3") (pinfunction "EXT_LO_DEC_3") (pintype "passive+no_connect"))
    )
    (net (code "58") (name "unconnected-(U4-GPO1{slash}ADD1-Pad15)") (class "Default")
      (node (ref "U4") (pin "15") (pinfunction "GPO1/ADD1_15") (pintype "passive+no_connect"))
    )
    (net (code "59") (name "unconnected-(U4-GPO2{slash}ADD2-Pad16)") (class "Default")
      (node (ref "U4") (pin "16") (pinfunction "GPO2/ADD2_16") (pintype "passive+no_connect"))
    )
    (net (code "60") (name "unconnected-(U4-GPO3{slash}FM-Pad25)") (class "Default")
      (node (ref "U4") (pin "25") (pinfunction "GPO3/FM_25") (pintype "passive+no_connect"))
    )
    (net (code "61") (name "unconnected-(U4-NC-Pad11)") (class "Default")
      (node (ref "U4") (pin "11") (pinfunction "NC_11") (pintype "passive"))
    )
    (net (code "62") (name "unconnected-(U4-NC-Pad13)") (class "Default")
      (node (ref "U4") (pin "13") (pinfunction "NC_13") (pintype "passive"))
    )
    (net (code "63") (name "unconnected-(U4-NC-Pad14)") (class "Default")
      (node (ref "U4") (pin "14") (pinfunction "NC_14") (pintype "passive"))
    )
    (net (code "64") (name "unconnected-(U4-NC-Pad17)") (class "Default")
      (node (ref "U4") (pin "17") (pinfunction "NC_17") (pintype "passive"))
    )
    (net (code "65") (name "unconnected-(U4-NC-Pad18)") (class "Default")
      (node (ref "U4") (pin "18") (pinfunction "NC_18") (pintype "passive"))
    )
    (net (code "66") (name "unconnected-(U4-NC-Pad20)") (class "Default")
      (node (ref "U4") (pin "20") (pinfunction "NC_20") (pintype "passive"))
    )
    (net (code "67") (name "unconnected-(U4-NC-Pad21)") (class "Default")
      (node (ref "U4") (pin "21") (pinfunction "NC_21") (pintype "passive"))
    )
  )
)
